# Rocketometer9250_2.net
KiCad netlist of a schematic drawn in EAGLE
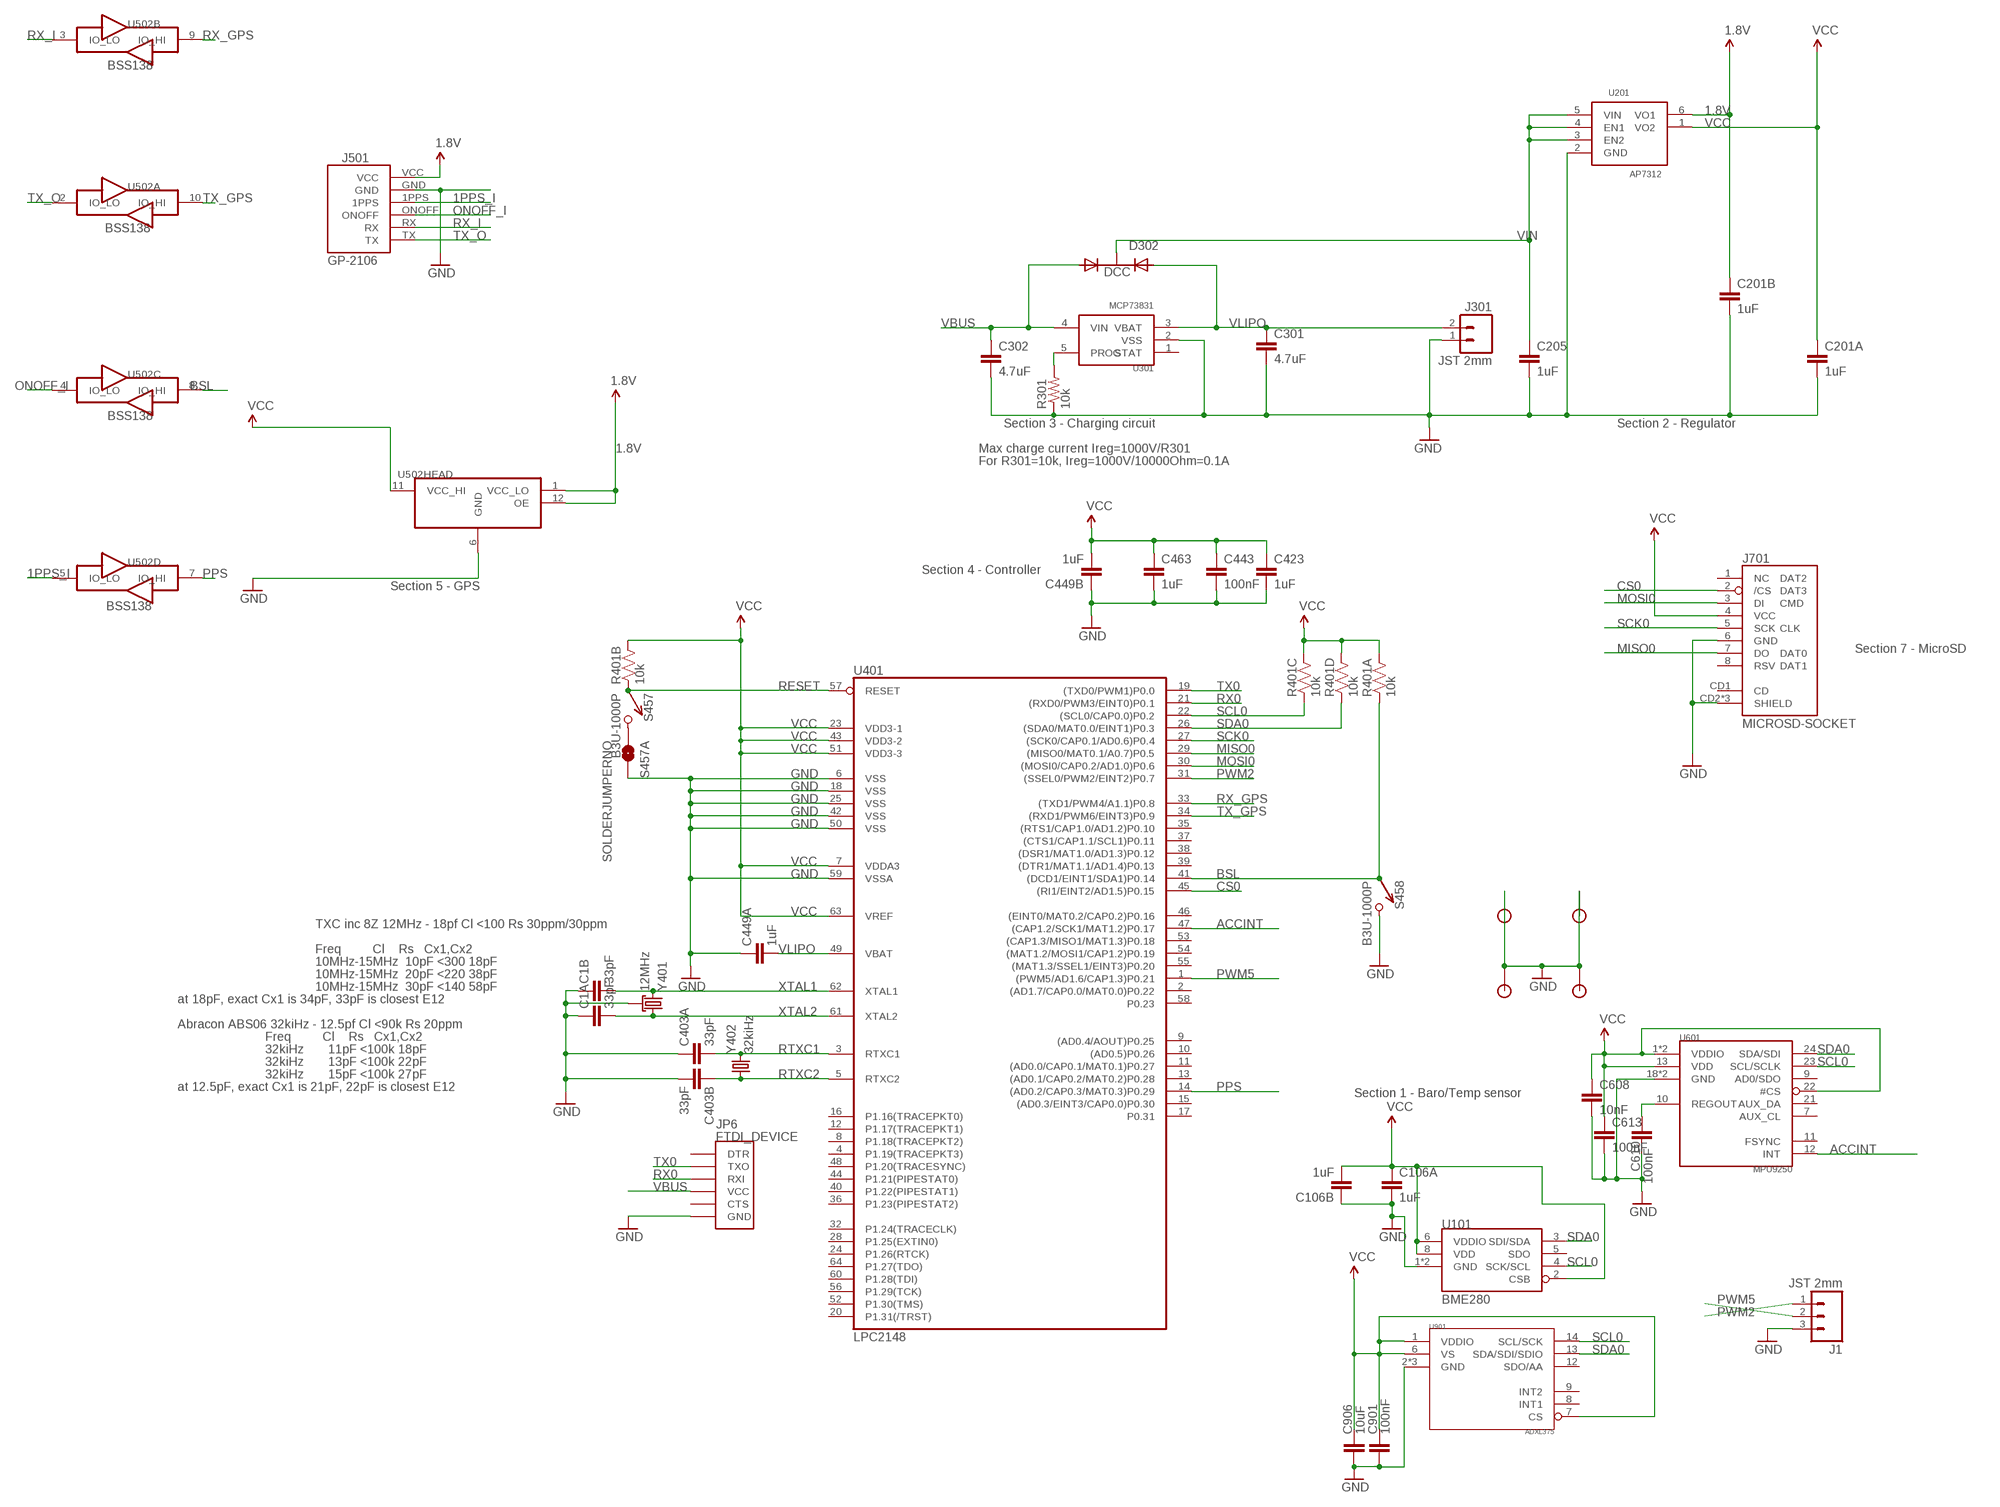
[diagram p0: schematic, sheet 1]

(export (version "E")
  (design (tool "Eeschema 10.0.6"))
  (components
    (comp (ref "C1")
      (value "33pF")
      (footprint "eagle-import:CKCM25")
      (libsource (lib "eagle-import") (part "CKCM25"))
    )
    (comp (ref "C106")
      (value "1uF")
      (footprint "eagle-import:CKCM25")
      (libsource (lib "eagle-import") (part "CKCM25"))
    )
    (comp (ref "C201")
      (value "1uF")
      (footprint "eagle-import:CKCM25")
      (libsource (lib "eagle-import") (part "CKCM25"))
    )
    (comp (ref "C205")
      (value "1uF")
      (footprint "eagle-import:0402-CAP")
      (libsource (lib "eagle-import") (part "CAP0402-CAP"))
    )
    (comp (ref "C301")
      (value "4.7uF")
      (footprint "eagle-import:0402-CAP")
      (libsource (lib "eagle-import") (part "CAP0402-CAP"))
    )
    (comp (ref "C302")
      (value "4.7uF")
      (footprint "eagle-import:0402-CAP")
      (libsource (lib "eagle-import") (part "CAP0402-CAP"))
    )
    (comp (ref "C403")
      (value "33pF")
      (footprint "eagle-import:CKCM25")
      (libsource (lib "eagle-import") (part "CKCM25"))
    )
    (comp (ref "C423")
      (value "1uF")
      (footprint "eagle-import:0402-CAP")
      (libsource (lib "eagle-import") (part "CAP0402-CAP"))
    )
    (comp (ref "C443")
      (value "100nF")
      (footprint "eagle-import:0402-CAP")
      (libsource (lib "eagle-import") (part "CAP0402-CAP"))
    )
    (comp (ref "C449")
      (value "1uF")
      (footprint "eagle-import:CKCM25")
      (libsource (lib "eagle-import") (part "CKCM25"))
    )
    (comp (ref "C463")
      (value "1uF")
      (footprint "eagle-import:0402-CAP")
      (libsource (lib "eagle-import") (part "CAP0402-CAP"))
    )
    (comp (ref "C608")
      (value "10nF")
      (footprint "eagle-import:0402-CAP")
      (libsource (lib "eagle-import") (part "CAP0402-CAP"))
    )
    (comp (ref "C610")
      (value "100nF")
      (footprint "eagle-import:0402-CAP")
      (libsource (lib "eagle-import") (part "CAP0402-CAP"))
    )
    (comp (ref "C613")
      (value "100nF")
      (footprint "eagle-import:0402-CAP")
      (libsource (lib "eagle-import") (part "CAP0402-CAP"))
    )
    (comp (ref "C901")
      (value "100nF")
      (footprint "eagle-import:0402-CAP")
      (libsource (lib "eagle-import") (part "SparkFun-Passives_CAP0402-CAP"))
    )
    (comp (ref "C906")
      (value "10uF")
      (footprint "eagle-import:0603-CAP")
      (libsource (lib "eagle-import") (part "CAP0603-CAP"))
    )
    (comp (ref "D302")
      (value "DCC")
      (footprint "eagle-import:SOT-23-3")
      (libsource (lib "eagle-import") (part "PMEG2005CT"))
    )
    (comp (ref "J1")
      (value "JST 2mm")
      (footprint "eagle-import:1X03_NO_SILK")
      (libsource (lib "eagle-import") (part "M031X03_NO_SILK"))
    )
    (comp (ref "J301")
      (value "JST 2mm")
      (footprint "eagle-import:1X02_NO_SILK")
      (libsource (lib "eagle-import") (part "M021X02_NO_SILK"))
    )
    (comp (ref "J501")
      (value "GP-2106")
      (footprint "eagle-import:GP-2106")
      (libsource (lib "eagle-import") (part "GP-2106"))
    )
    (comp (ref "J701")
      (value "MICROSD-SOCKET")
      (footprint "eagle-import:MICROSD-SOCKET-PP")
      (libsource (lib "eagle-import") (part "MICROSD-SOCKET"))
    )
    (comp (ref "JP1")
      (value "STANDOFF")
      (footprint "eagle-import:STANDOFF")
      (libsource (lib "eagle-import") (part "STANDOFF"))
    )
    (comp (ref "JP2")
      (value "STANDOFF")
      (footprint "eagle-import:STANDOFF")
      (libsource (lib "eagle-import") (part "STANDOFF"))
    )
    (comp (ref "JP4")
      (value "STANDOFF")
      (footprint "eagle-import:STANDOFF")
      (libsource (lib "eagle-import") (part "STANDOFF"))
    )
    (comp (ref "JP5")
      (value "STANDOFF")
      (footprint "eagle-import:STANDOFF")
      (libsource (lib "eagle-import") (part "STANDOFF"))
    )
    (comp (ref "JP6")
      (value "FTDI_DEVICE")
      (footprint "eagle-import:FTDI_DEVICE_SIDE")
      (libsource (lib "eagle-import") (part "FTDI_DEVICE"))
    )
    (comp (ref "R301")
      (value "10k")
      (footprint "eagle-import:0402-RES")
      (libsource (lib "eagle-import") (part "RESISTOR0402-RES"))
    )
    (comp (ref "R401")
      (value "10k")
      (footprint "eagle-import:CRA04")
      (fields (field (name "DIGIKEY") "CRA4S810KCT-ND"))
      (libsource (lib "eagle-import") (part "RP404"))
    )
    (comp (ref "S457")
      (value "B3U-1000P")
      (footprint "eagle-import:B3U-1000P")
      (libsource (lib "eagle-import") (part "B3U-1000P"))
    )
    (comp (ref "S457A")
      (value "SOLDERJUMPERNO")
      (footprint "eagle-import:SJ_2S-NO")
      (libsource (lib "eagle-import") (part "SOLDERJUMPERNO"))
    )
    (comp (ref "S458")
      (value "B3U-1000P")
      (footprint "eagle-import:B3U-1000P")
      (libsource (lib "eagle-import") (part "B3U-1000P"))
    )
    (comp (ref "U101")
      (value "BME280")
      (footprint "eagle-import:BME280")
      (libsource (lib "eagle-import") (part "BME280"))
    )
    (comp (ref "U201")
      (value "AP7312")
      (footprint "eagle-import:SOT-23-6")
      (libsource (lib "eagle-import") (part "AP73X2"))
    )
    (comp (ref "U301")
      (value "MCP73831")
      (footprint "eagle-import:SOT-23-5")
      (libsource (lib "eagle-import") (part "MCP73831"))
    )
    (comp (ref "U401")
      (value "LPC2148")
      (footprint "eagle-import:SQFP-S-10X10-64")
      (libsource (lib "eagle-import") (part "LPC213X"))
    )
    (comp (ref "U502")
      (value "TXB0104RUT")
      (footprint "eagle-import:R-PUQFN-N12")
      (libsource (lib "eagle-import") (part "TXB0104RUT"))
    )
    (comp (ref "U601")
      (value "MPU9250")
      (footprint "eagle-import:LQFN_3MM_3MM")
      (libsource (lib "eagle-import") (part "MPU9250"))
    )
    (comp (ref "U901")
      (value "ADXL375")
      (footprint "eagle-import:ADXL375")
      (libsource (lib "eagle-import") (part "ADXL375"))
    )
    (comp (ref "Y401")
      (value "12MHz")
      (footprint "eagle-import:CRYSTAL_SMD_2MM_2_5MM")
      (libsource (lib "eagle-import") (part "CX2520"))
    )
    (comp (ref "Y402")
      (value "32kiHz")
      (footprint "eagle-import:ABS06")
      (libsource (lib "eagle-import") (part "ABS06"))
    )
  )
  (nets
    (net (code "1") (name "/1PPS_I") (class "Default")
      (node (ref "J501") (pin "1PPS") (pinfunction "1PPS_1PPS") (pintype "bidirectional"))
      (node (ref "U502") (pin "5") (pinfunction "IO_LO_5") (pintype "bidirectional"))
    )
    (net (code "2") (name "/ACCINT") (class "Default")
      (node (ref "U401") (pin "47") (pinfunction "(CAP1.2/SCK1/MAT1.2)P0.17_47") (pintype "bidirectional"))
      (node (ref "U601") (pin "12") (pinfunction "INT_12") (pintype "bidirectional"))
    )
    (net (code "3") (name "/BSL") (class "Default")
      (node (ref "R401") (pin "1") (pinfunction "1_1") (pintype "passive"))
      (node (ref "S458") (pin "P$1") (pinfunction "1_P$1") (pintype "bidirectional"))
      (node (ref "U401") (pin "41") (pinfunction "(DCD1/EINT1/SDA1)P0.14_41") (pintype "bidirectional"))
      (node (ref "U502") (pin "8") (pinfunction "IO_HI_8") (pintype "bidirectional"))
    )
    (net (code "4") (name "/CS0") (class "Default")
      (node (ref "J701") (pin "2") (pinfunction "/CS_2") (pintype "bidirectional"))
      (node (ref "U401") (pin "45") (pinfunction "(RI1/EINT2/AD1.5)P0.15_45") (pintype "bidirectional"))
    )
    (net (code "5") (name "/MISO0") (class "Default")
      (node (ref "J701") (pin "7") (pinfunction "DO_7") (pintype "bidirectional"))
      (node (ref "U401") (pin "29") (pinfunction "(MISO0/MAT0.1/A0.7)P0.5_29") (pintype "bidirectional"))
    )
    (net (code "6") (name "/MOSI0") (class "Default")
      (node (ref "J701") (pin "3") (pinfunction "DI_3") (pintype "bidirectional"))
      (node (ref "U401") (pin "30") (pinfunction "(MOSI0/CAP0.2/AD1.0)P0.6_30") (pintype "bidirectional"))
    )
    (net (code "7") (name "/ONOFF_I") (class "Default")
      (node (ref "J501") (pin "ONOFF") (pinfunction "ONOFF_ONOFF") (pintype "bidirectional"))
      (node (ref "U502") (pin "4") (pinfunction "IO_LO_4") (pintype "bidirectional"))
    )
    (net (code "8") (name "/PPS") (class "Default")
      (node (ref "U401") (pin "14") (pinfunction "(AD0.2/CAP0.3/MAT0.3)P0.29_14") (pintype "bidirectional"))
      (node (ref "U502") (pin "7") (pinfunction "IO_HI_7") (pintype "bidirectional"))
    )
    (net (code "9") (name "/PWM2") (class "Default")
      (node (ref "J1") (pin "1") (pinfunction "1_1") (pintype "passive"))
      (node (ref "U401") (pin "31") (pinfunction "(SSEL0/PWM2/EINT2)P0.7_31") (pintype "bidirectional"))
    )
    (net (code "10") (name "/PWM5") (class "Default")
      (node (ref "J1") (pin "2") (pinfunction "2_2") (pintype "passive"))
      (node (ref "U401") (pin "1") (pinfunction "(PWM5/AD1.6/CAP1.3)P0.21_1") (pintype "bidirectional"))
    )
    (net (code "11") (name "/RESET") (class "Default")
      (node (ref "R401") (pin "2") (pinfunction "1_2") (pintype "passive"))
      (node (ref "S457") (pin "P$1") (pinfunction "1_P$1") (pintype "bidirectional"))
      (node (ref "U401") (pin "57") (pinfunction "RESET_57") (pintype "input"))
    )
    (net (code "12") (name "/RTXC1") (class "Default")
      (node (ref "C403") (pin "4") (pinfunction "2_4") (pintype "passive"))
      (node (ref "U401") (pin "3") (pinfunction "RTXC1_3") (pintype "input"))
      (node (ref "Y402") (pin "2") (pinfunction "2_2") (pintype "passive"))
    )
    (net (code "13") (name "/RTXC2") (class "Default")
      (node (ref "C403") (pin "2") (pinfunction "1_2") (pintype "passive"))
      (node (ref "U401") (pin "5") (pinfunction "RTXC2_5") (pintype "output"))
      (node (ref "Y402") (pin "1") (pinfunction "1_1") (pintype "passive"))
    )
    (net (code "14") (name "/RX0") (class "Default")
      (node (ref "JP6") (pin "P$3") (pinfunction "RXI_P$3") (pintype "bidirectional"))
      (node (ref "U401") (pin "21") (pinfunction "(RXD0/PWM3/EINT0)P0.1_21") (pintype "bidirectional"))
    )
    (net (code "15") (name "/RX_GPS") (class "Default")
      (node (ref "U401") (pin "33") (pinfunction "(TXD1/PWM4/A1.1)P0.8_33") (pintype "bidirectional"))
      (node (ref "U502") (pin "9") (pinfunction "IO_HI_9") (pintype "bidirectional"))
    )
    (net (code "16") (name "/RX_I") (class "Default")
      (node (ref "J501") (pin "RX") (pinfunction "RX_RX") (pintype "bidirectional"))
      (node (ref "U502") (pin "3") (pinfunction "IO_LO_3") (pintype "bidirectional"))
    )
    (net (code "17") (name "/SCK0") (class "Default")
      (node (ref "J701") (pin "5") (pinfunction "SCK_5") (pintype "bidirectional"))
      (node (ref "U401") (pin "27") (pinfunction "(SCK0/CAP0.1/AD0.6)P0.4_27") (pintype "bidirectional"))
    )
    (net (code "18") (name "/SCL0") (class "Default")
      (node (ref "R401") (pin "3") (pinfunction "1_3") (pintype "passive"))
      (node (ref "U101") (pin "4") (pinfunction "SCK/SCL_4") (pintype "input"))
      (node (ref "U401") (pin "22") (pinfunction "(SCL0/CAP0.0)P0.2_22") (pintype "bidirectional"))
      (node (ref "U601") (pin "23") (pinfunction "SCL/SCLK_23") (pintype "bidirectional"))
      (node (ref "U901") (pin "14") (pinfunction "SCL/SCK_14") (pintype "input"))
    )
    (net (code "19") (name "/SDA0") (class "Default")
      (node (ref "R401") (pin "4") (pinfunction "1_4") (pintype "passive"))
      (node (ref "U101") (pin "3") (pinfunction "SDI/SDA_3") (pintype "bidirectional"))
      (node (ref "U401") (pin "26") (pinfunction "(SDA0/MAT0.0/EINT1)P0.3_26") (pintype "bidirectional"))
      (node (ref "U601") (pin "24") (pinfunction "SDA/SDI_24") (pintype "bidirectional"))
      (node (ref "U901") (pin "13") (pinfunction "SDA/SDI/SDIO_13") (pintype "bidirectional"))
    )
    (net (code "20") (name "/TX0") (class "Default")
      (node (ref "JP6") (pin "P$2") (pinfunction "TXO_P$2") (pintype "bidirectional"))
      (node (ref "U401") (pin "19") (pinfunction "(TXD0/PWM1)P0.0_19") (pintype "bidirectional"))
    )
    (net (code "21") (name "/TX_GPS") (class "Default")
      (node (ref "U401") (pin "34") (pinfunction "(RXD1/PWM6/EINT3)P0.9_34") (pintype "bidirectional"))
      (node (ref "U502") (pin "10") (pinfunction "IO_HI_10") (pintype "bidirectional"))
    )
    (net (code "22") (name "/TX_O") (class "Default")
      (node (ref "J501") (pin "TX") (pinfunction "TX_TX") (pintype "bidirectional"))
      (node (ref "U502") (pin "2") (pinfunction "IO_LO_2") (pintype "bidirectional"))
    )
    (net (code "23") (name "/VBUS") (class "Default")
      (node (ref "C302") (pin "1") (pinfunction "1_1") (pintype "passive"))
      (node (ref "D302") (pin "1") (pinfunction "A1_1") (pintype "passive"))
      (node (ref "JP6") (pin "P$4") (pinfunction "VCC_P$4") (pintype "bidirectional"))
      (node (ref "U301") (pin "4") (pinfunction "VIN_4") (pintype "power_in"))
    )
    (net (code "24") (name "/VIN") (class "Default")
      (node (ref "C205") (pin "1") (pinfunction "1_1") (pintype "passive"))
      (node (ref "D302") (pin "3") (pinfunction "K_3") (pintype "passive"))
      (node (ref "U201") (pin "3") (pinfunction "EN2_3") (pintype "bidirectional"))
      (node (ref "U201") (pin "4") (pinfunction "EN1_4") (pintype "bidirectional"))
      (node (ref "U201") (pin "5") (pinfunction "VIN_5") (pintype "bidirectional"))
    )
    (net (code "25") (name "/VLIPO") (class "Default")
      (node (ref "C301") (pin "1") (pinfunction "1_1") (pintype "passive"))
      (node (ref "C449") (pin "4") (pinfunction "2_4") (pintype "passive"))
      (node (ref "D302") (pin "2") (pinfunction "A2_2") (pintype "passive"))
      (node (ref "J301") (pin "2") (pinfunction "2_2") (pintype "passive"))
      (node (ref "U301") (pin "3") (pinfunction "VBAT_3") (pintype "power_in"))
      (node (ref "U401") (pin "49") (pinfunction "VBAT_49") (pintype "power_in"))
    )
    (net (code "26") (name "/XTAL1") (class "Default")
      (node (ref "C1") (pin "3") (pinfunction "2_3") (pintype "passive"))
      (node (ref "U401") (pin "62") (pinfunction "XTAL1_62") (pintype "input"))
      (node (ref "Y401") (pin "3") (pinfunction "2_3") (pintype "passive"))
    )
    (net (code "27") (name "/XTAL2") (class "Default")
      (node (ref "C1") (pin "4") (pinfunction "2_4") (pintype "passive"))
      (node (ref "U401") (pin "61") (pinfunction "XTAL2_61") (pintype "output"))
      (node (ref "Y401") (pin "1") (pinfunction "1_1") (pintype "passive"))
    )
    (net (code "28") (name "1.8V") (class "Default")
      (node (ref "C201") (pin "2") (pinfunction "1_2") (pintype "passive"))
      (node (ref "J501") (pin "VCC") (pinfunction "VCC_VCC") (pintype "bidirectional"))
      (node (ref "U201") (pin "6") (pinfunction "VO1_6") (pintype "bidirectional"))
      (node (ref "U502") (pin "1") (pinfunction "VCC_LO_1") (pintype "power_in"))
      (node (ref "U502") (pin "12") (pinfunction "OE_12") (pintype "bidirectional"))
    )
    (net (code "29") (name "GND") (class "Default")
      (node (ref "C1") (pin "1") (pinfunction "1_1") (pintype "passive"))
      (node (ref "C1") (pin "2") (pinfunction "1_2") (pintype "passive"))
      (node (ref "C106") (pin "2") (pinfunction "1_2") (pintype "passive"))
      (node (ref "C106") (pin "4") (pinfunction "2_4") (pintype "passive"))
      (node (ref "C201") (pin "3") (pinfunction "2_3") (pintype "passive"))
      (node (ref "C201") (pin "4") (pinfunction "2_4") (pintype "passive"))
      (node (ref "C205") (pin "2") (pinfunction "2_2") (pintype "passive"))
      (node (ref "C301") (pin "2") (pinfunction "2_2") (pintype "passive"))
      (node (ref "C302") (pin "2") (pinfunction "2_2") (pintype "passive"))
      (node (ref "C403") (pin "1") (pinfunction "1_1") (pintype "passive"))
      (node (ref "C403") (pin "3") (pinfunction "2_3") (pintype "passive"))
      (node (ref "C423") (pin "2") (pinfunction "2_2") (pintype "passive"))
      (node (ref "C443") (pin "2") (pinfunction "2_2") (pintype "passive"))
      (node (ref "C449") (pin "1") (pinfunction "1_1") (pintype "passive"))
      (node (ref "C449") (pin "2") (pinfunction "1_2") (pintype "passive"))
      (node (ref "C463") (pin "2") (pinfunction "2_2") (pintype "passive"))
      (node (ref "C608") (pin "2") (pinfunction "2_2") (pintype "passive"))
      (node (ref "C610") (pin "2") (pinfunction "2_2") (pintype "passive"))
      (node (ref "C613") (pin "2") (pinfunction "2_2") (pintype "passive"))
      (node (ref "C901") (pin "2") (pinfunction "2_2") (pintype "passive"))
      (node (ref "C906") (pin "2") (pinfunction "2_2") (pintype "passive"))
      (node (ref "J1") (pin "3") (pinfunction "3_3") (pintype "passive"))
      (node (ref "J301") (pin "1") (pinfunction "1_1") (pintype "passive"))
      (node (ref "J501") (pin "GND") (pinfunction "GND_GND") (pintype "bidirectional"))
      (node (ref "J701") (pin "6") (pinfunction "GND_6") (pintype "bidirectional"))
      (node (ref "J701") (pin "CD2") (pinfunction "SHIELD_CD2") (pintype "bidirectional"))
      (node (ref "J701") (pin "GND1") (pinfunction "SHIELD_GND1") (pintype "bidirectional"))
      (node (ref "J701") (pin "GND3") (pinfunction "SHIELD_GND3") (pintype "bidirectional"))
      (node (ref "JP1") (pin "P$1") (pinfunction "P$1_P$1") (pintype "bidirectional"))
      (node (ref "JP2") (pin "P$1") (pinfunction "P$1_P$1") (pintype "bidirectional"))
      (node (ref "JP4") (pin "P$1") (pinfunction "P$1_P$1") (pintype "bidirectional"))
      (node (ref "JP5") (pin "P$1") (pinfunction "P$1_P$1") (pintype "bidirectional"))
      (node (ref "JP6") (pin "P$6") (pinfunction "GND_P$6") (pintype "bidirectional"))
      (node (ref "R301") (pin "1") (pinfunction "1_1") (pintype "passive"))
      (node (ref "S457A") (pin "2") (pinfunction "2_2") (pintype "passive"))
      (node (ref "S458") (pin "P$2") (pinfunction "2_P$2") (pintype "bidirectional"))
      (node (ref "U101") (pin "1") (pinfunction "GND_1") (pintype "power_in"))
      (node (ref "U101") (pin "7") (pinfunction "GND_7") (pintype "power_in"))
      (node (ref "U201") (pin "2") (pinfunction "GND_2") (pintype "bidirectional"))
      (node (ref "U301") (pin "2") (pinfunction "VSS_2") (pintype "power_in"))
      (node (ref "U401") (pin "18") (pinfunction "VSS_18") (pintype "power_in"))
      (node (ref "U401") (pin "25") (pinfunction "VSS_25") (pintype "power_in"))
      (node (ref "U401") (pin "42") (pinfunction "VSS_42") (pintype "power_in"))
      (node (ref "U401") (pin "50") (pinfunction "VSS_50") (pintype "power_in"))
      (node (ref "U401") (pin "59") (pinfunction "VSSA_59") (pintype "power_in"))
      (node (ref "U401") (pin "6") (pinfunction "VSS_6") (pintype "power_in"))
      (node (ref "U502") (pin "6") (pinfunction "GND_6") (pintype "power_in"))
      (node (ref "U601") (pin "18") (pinfunction "GND_18") (pintype "bidirectional"))
      (node (ref "U601") (pin "20") (pinfunction "GND_20") (pintype "bidirectional"))
      (node (ref "U901") (pin "2") (pinfunction "GND_2") (pintype "power_in"))
      (node (ref "U901") (pin "4") (pinfunction "GND_4") (pintype "power_in"))
      (node (ref "U901") (pin "5") (pinfunction "GND_5") (pintype "power_in"))
      (node (ref "Y401") (pin "2") (pinfunction "GND_2") (pintype "passive"))
      (node (ref "Y401") (pin "4") (pinfunction "GND_4") (pintype "passive"))
    )
    (net (code "30") (name "Net-(S457-2)") (class "Default")
      (node (ref "S457") (pin "P$2") (pinfunction "2_P$2") (pintype "bidirectional"))
      (node (ref "S457A") (pin "1") (pinfunction "1_1") (pintype "passive"))
    )
    (net (code "31") (name "Net-(U301-PROG)") (class "Default")
      (node (ref "R301") (pin "2") (pinfunction "2_2") (pintype "passive"))
      (node (ref "U301") (pin "5") (pinfunction "PROG_5") (pintype "passive"))
    )
    (net (code "32") (name "Net-(U601-REGOUT)") (class "Default")
      (node (ref "C610") (pin "1") (pinfunction "1_1") (pintype "passive"))
      (node (ref "U601") (pin "10") (pinfunction "REGOUT_10") (pintype "bidirectional"))
    )
    (net (code "33") (name "VCC") (class "Default")
      (node (ref "C106") (pin "1") (pinfunction "1_1") (pintype "passive"))
      (node (ref "C106") (pin "3") (pinfunction "2_3") (pintype "passive"))
      (node (ref "C201") (pin "1") (pinfunction "1_1") (pintype "passive"))
      (node (ref "C423") (pin "1") (pinfunction "1_1") (pintype "passive"))
      (node (ref "C443") (pin "1") (pinfunction "1_1") (pintype "passive"))
      (node (ref "C449") (pin "3") (pinfunction "2_3") (pintype "passive"))
      (node (ref "C463") (pin "1") (pinfunction "1_1") (pintype "passive"))
      (node (ref "C608") (pin "1") (pinfunction "1_1") (pintype "passive"))
      (node (ref "C613") (pin "1") (pinfunction "1_1") (pintype "passive"))
      (node (ref "C901") (pin "1") (pinfunction "1_1") (pintype "passive"))
      (node (ref "C906") (pin "1") (pinfunction "1_1") (pintype "passive"))
      (node (ref "J701") (pin "4") (pinfunction "VCC_4") (pintype "bidirectional"))
      (node (ref "R401") (pin "5") (pinfunction "2_5") (pintype "passive"))
      (node (ref "R401") (pin "6") (pinfunction "2_6") (pintype "passive"))
      (node (ref "R401") (pin "7") (pinfunction "2_7") (pintype "passive"))
      (node (ref "R401") (pin "8") (pinfunction "2_8") (pintype "passive"))
      (node (ref "U101") (pin "2") (pinfunction "CSB_2") (pintype "input"))
      (node (ref "U101") (pin "6") (pinfunction "VDDIO_6") (pintype "power_in"))
      (node (ref "U101") (pin "8") (pinfunction "VDD_8") (pintype "power_in"))
      (node (ref "U201") (pin "1") (pinfunction "VO2_1") (pintype "bidirectional"))
      (node (ref "U401") (pin "23") (pinfunction "VDD3-1_23") (pintype "power_in"))
      (node (ref "U401") (pin "43") (pinfunction "VDD3-2_43") (pintype "power_in"))
      (node (ref "U401") (pin "51") (pinfunction "VDD3-3_51") (pintype "power_in"))
      (node (ref "U401") (pin "63") (pinfunction "VREF_63") (pintype "input"))
      (node (ref "U401") (pin "7") (pinfunction "VDDA3_7") (pintype "power_in"))
      (node (ref "U502") (pin "11") (pinfunction "VCC_HI_11") (pintype "power_in"))
      (node (ref "U601") (pin "1") (pinfunction "VDDIO_1") (pintype "bidirectional"))
      (node (ref "U601") (pin "13") (pinfunction "VDD_13") (pintype "bidirectional"))
      (node (ref "U601") (pin "22") (pinfunction "#CS_22") (pintype "bidirectional"))
      (node (ref "U601") (pin "8") (pinfunction "VDDIO_8") (pintype "bidirectional"))
      (node (ref "U901") (pin "1") (pinfunction "VDDIO_1") (pintype "power_in"))
      (node (ref "U901") (pin "6") (pinfunction "VS_6") (pintype "power_in"))
      (node (ref "U901") (pin "7") (pinfunction "CS_7") (pintype "input"))
    )
    (net (code "34") (name "unconnected-(J701-CD-PadCD1)") (class "Default")
      (node (ref "J701") (pin "CD1") (pinfunction "CD_CD1") (pintype "bidirectional"))
    )
    (net (code "35") (name "unconnected-(J701-NC-Pad1)") (class "Default")
      (node (ref "J701") (pin "1") (pinfunction "NC_1") (pintype "bidirectional"))
    )
    (net (code "36") (name "unconnected-(J701-RSV-Pad8)") (class "Default")
      (node (ref "J701") (pin "8") (pinfunction "RSV_8") (pintype "bidirectional"))
    )
    (net (code "37") (name "unconnected-(JP6-CTS-PadP$5)") (class "Default")
      (node (ref "JP6") (pin "P$5") (pinfunction "CTS_P$5") (pintype "bidirectional"))
    )
    (net (code "38") (name "unconnected-(JP6-DTR-PadP$1)") (class "Default")
      (node (ref "JP6") (pin "P$1") (pinfunction "DTR_P$1") (pintype "bidirectional"))
    )
    (net (code "39") (name "unconnected-(U101-SDO-Pad5)") (class "Default")
      (node (ref "U101") (pin "5") (pinfunction "SDO_5") (pintype "bidirectional"))
    )
    (net (code "40") (name "unconnected-(U301-STAT-Pad1)") (class "Default")
      (node (ref "U301") (pin "1") (pinfunction "STAT_1") (pintype "bidirectional"))
    )
    (net (code "41") (name "unconnected-(U401-(AD0.0{slash}CAP0.1{slash}MAT0.1)P0.27-Pad11)") (class "Default")
      (node (ref "U401") (pin "11") (pinfunction "(AD0.0/CAP0.1/MAT0.1)P0.27_11") (pintype "bidirectional"))
    )
    (net (code "42") (name "unconnected-(U401-(AD0.1{slash}CAP0.2{slash}MAT0.2)P0.28-Pad13)") (class "Default")
      (node (ref "U401") (pin "13") (pinfunction "(AD0.1/CAP0.2/MAT0.2)P0.28_13") (pintype "bidirectional"))
    )
    (net (code "43") (name "unconnected-(U401-(AD0.3{slash}EINT3{slash}CAP0.0)P0.30-Pad15)") (class "Default")
      (node (ref "U401") (pin "15") (pinfunction "(AD0.3/EINT3/CAP0.0)P0.30_15") (pintype "bidirectional"))
    )
    (net (code "44") (name "unconnected-(U401-(AD0.4{slash}AOUT)P0.25-Pad9)") (class "Default")
      (node (ref "U401") (pin "9") (pinfunction "(AD0.4/AOUT)P0.25_9") (pintype "bidirectional"))
    )
    (net (code "45") (name "unconnected-(U401-(AD0.5)P0.26-Pad10)") (class "Default")
      (node (ref "U401") (pin "10") (pinfunction "(AD0.5)P0.26_10") (pintype "bidirectional"))
    )
    (net (code "46") (name "unconnected-(U401-(AD1.7{slash}CAP0.0{slash}MAT0.0)P0.22-Pad2)") (class "Default")
      (node (ref "U401") (pin "2") (pinfunction "(AD1.7/CAP0.0/MAT0.0)P0.22_2") (pintype "bidirectional"))
    )
    (net (code "47") (name "unconnected-(U401-(CAP1.3{slash}MISO1{slash}MAT1.3)P0.18-Pad53)") (class "Default")
      (node (ref "U401") (pin "53") (pinfunction "(CAP1.3/MISO1/MAT1.3)P0.18_53") (pintype "bidirectional"))
    )
    (net (code "48") (name "unconnected-(U401-(CTS1{slash}CAP1.1{slash}SCL1)P0.11-Pad37)") (class "Default")
      (node (ref "U401") (pin "37") (pinfunction "(CTS1/CAP1.1/SCL1)P0.11_37") (pintype "bidirectional"))
    )
    (net (code "49") (name "unconnected-(U401-(DSR1{slash}MAT1.0{slash}AD1.3)P0.12-Pad38)") (class "Default")
      (node (ref "U401") (pin "38") (pinfunction "(DSR1/MAT1.0/AD1.3)P0.12_38") (pintype "bidirectional"))
    )
    (net (code "50") (name "unconnected-(U401-(DTR1{slash}MAT1.1{slash}AD1.4)P0.13-Pad39)") (class "Default")
      (node (ref "U401") (pin "39") (pinfunction "(DTR1/MAT1.1/AD1.4)P0.13_39") (pintype "bidirectional"))
    )
    (net (code "51") (name "unconnected-(U401-(EINT0{slash}MAT0.2{slash}CAP0.2)P0.16-Pad46)") (class "Default")
      (node (ref "U401") (pin "46") (pinfunction "(EINT0/MAT0.2/CAP0.2)P0.16_46") (pintype "bidirectional"))
    )
    (net (code "52") (name "unconnected-(U401-(MAT1.2{slash}MOSI1{slash}CAP1.2)P0.19-Pad54)") (class "Default")
      (node (ref "U401") (pin "54") (pinfunction "(MAT1.2/MOSI1/CAP1.2)P0.19_54") (pintype "bidirectional"))
    )
    (net (code "53") (name "unconnected-(U401-(MAT1.3{slash}SSEL1{slash}EINT3)P0.20-Pad55)") (class "Default")
      (node (ref "U401") (pin "55") (pinfunction "(MAT1.3/SSEL1/EINT3)P0.20_55") (pintype "bidirectional"))
    )
    (net (code "54") (name "unconnected-(U401-(RTS1{slash}CAP1.0{slash}AD1.2)P0.10-Pad35)") (class "Default")
      (node (ref "U401") (pin "35") (pinfunction "(RTS1/CAP1.0/AD1.2)P0.10_35") (pintype "bidirectional"))
    )
    (net (code "55") (name "unconnected-(U401-P0.23-Pad58)") (class "Default")
      (node (ref "U401") (pin "58") (pinfunction "P0.23_58") (pintype "bidirectional"))
    )
    (net (code "56") (name "unconnected-(U401-P0.31-Pad17)") (class "Default")
      (node (ref "U401") (pin "17") (pinfunction "P0.31_17") (pintype "output"))
    )
    (net (code "57") (name "unconnected-(U401-P1.16(TRACEPKT0)-Pad16)") (class "Default")
      (node (ref "U401") (pin "16") (pinfunction "P1.16(TRACEPKT0)_16") (pintype "bidirectional"))
    )
    (net (code "58") (name "unconnected-(U401-P1.17(TRACEPKT1)-Pad12)") (class "Default")
      (node (ref "U401") (pin "12") (pinfunction "P1.17(TRACEPKT1)_12") (pintype "bidirectional"))
    )
    (net (code "59") (name "unconnected-(U401-P1.18(TRACEPKT2)-Pad8)") (class "Default")
      (node (ref "U401") (pin "8") (pinfunction "P1.18(TRACEPKT2)_8") (pintype "bidirectional"))
    )
    (net (code "60") (name "unconnected-(U401-P1.19(TRACEPKT3)-Pad4)") (class "Default")
      (node (ref "U401") (pin "4") (pinfunction "P1.19(TRACEPKT3)_4") (pintype "bidirectional"))
    )
    (net (code "61") (name "unconnected-(U401-P1.20(TRACESYNC)-Pad48)") (class "Default")
      (node (ref "U401") (pin "48") (pinfunction "P1.20(TRACESYNC)_48") (pintype "bidirectional"))
    )
    (net (code "62") (name "unconnected-(U401-P1.21(PIPESTAT0)-Pad44)") (class "Default")
      (node (ref "U401") (pin "44") (pinfunction "P1.21(PIPESTAT0)_44") (pintype "bidirectional"))
    )
    (net (code "63") (name "unconnected-(U401-P1.22(PIPESTAT1)-Pad40)") (class "Default")
      (node (ref "U401") (pin "40") (pinfunction "P1.22(PIPESTAT1)_40") (pintype "bidirectional"))
    )
    (net (code "64") (name "unconnected-(U401-P1.23(PIPESTAT2)-Pad36)") (class "Default")
      (node (ref "U401") (pin "36") (pinfunction "P1.23(PIPESTAT2)_36") (pintype "bidirectional"))
    )
    (net (code "65") (name "unconnected-(U401-P1.24(TRACECLK)-Pad32)") (class "Default")
      (node (ref "U401") (pin "32") (pinfunction "P1.24(TRACECLK)_32") (pintype "bidirectional"))
    )
    (net (code "66") (name "unconnected-(U401-P1.25(EXTIN0)-Pad28)") (class "Default")
      (node (ref "U401") (pin "28") (pinfunction "P1.25(EXTIN0)_28") (pintype "bidirectional"))
    )
    (net (code "67") (name "unconnected-(U401-P1.26(RTCK)-Pad24)") (class "Default")
      (node (ref "U401") (pin "24") (pinfunction "P1.26(RTCK)_24") (pintype "bidirectional"))
    )
    (net (code "68") (name "unconnected-(U401-P1.27(TDO)-Pad64)") (class "Default")
      (node (ref "U401") (pin "64") (pinfunction "P1.27(TDO)_64") (pintype "bidirectional"))
    )
    (net (code "69") (name "unconnected-(U401-P1.28(TDI)-Pad60)") (class "Default")
      (node (ref "U401") (pin "60") (pinfunction "P1.28(TDI)_60") (pintype "bidirectional"))
    )
    (net (code "70") (name "unconnected-(U401-P1.29(TCK)-Pad56)") (class "Default")
      (node (ref "U401") (pin "56") (pinfunction "P1.29(TCK)_56") (pintype "bidirectional"))
    )
    (net (code "71") (name "unconnected-(U401-P1.30(TMS)-Pad52)") (class "Default")
      (node (ref "U401") (pin "52") (pinfunction "P1.30(TMS)_52") (pintype "bidirectional"))
    )
    (net (code "72") (name "unconnected-(U401-P1.31({slash}TRST)-Pad20)") (class "Default")
      (node (ref "U401") (pin "20") (pinfunction "P1.31(/TRST)_20") (pintype "bidirectional"))
    )
    (net (code "73") (name "unconnected-(U601-AD0{slash}SDO-Pad9)") (class "Default")
      (node (ref "U601") (pin "9") (pinfunction "AD0/SDO_9") (pintype "bidirectional"))
    )
    (net (code "74") (name "unconnected-(U601-AUX_CL-Pad7)") (class "Default")
      (node (ref "U601") (pin "7") (pinfunction "AUX_CL_7") (pintype "bidirectional"))
    )
    (net (code "75") (name "unconnected-(U601-AUX_DA-Pad21)") (class "Default")
      (node (ref "U601") (pin "21") (pinfunction "AUX_DA_21") (pintype "bidirectional"))
    )
    (net (code "76") (name "unconnected-(U601-FSYNC-Pad11)") (class "Default")
      (node (ref "U601") (pin "11") (pinfunction "FSYNC_11") (pintype "bidirectional"))
    )
    (net (code "77") (name "unconnected-(U901-INT1-Pad8)") (class "Default")
      (node (ref "U901") (pin "8") (pinfunction "INT1_8") (pintype "output"))
    )
    (net (code "78") (name "unconnected-(U901-INT2-Pad9)") (class "Default")
      (node (ref "U901") (pin "9") (pinfunction "INT2_9") (pintype "output"))
    )
    (net (code "79") (name "unconnected-(U901-SDO{slash}AA-Pad12)") (class "Default")
      (node (ref "U901") (pin "12") (pinfunction "SDO/AA_12") (pintype "bidirectional"))
    )
  )
)
